# 1-MCU.net
KiCad netlist of a schematic drawn in Altium Designer
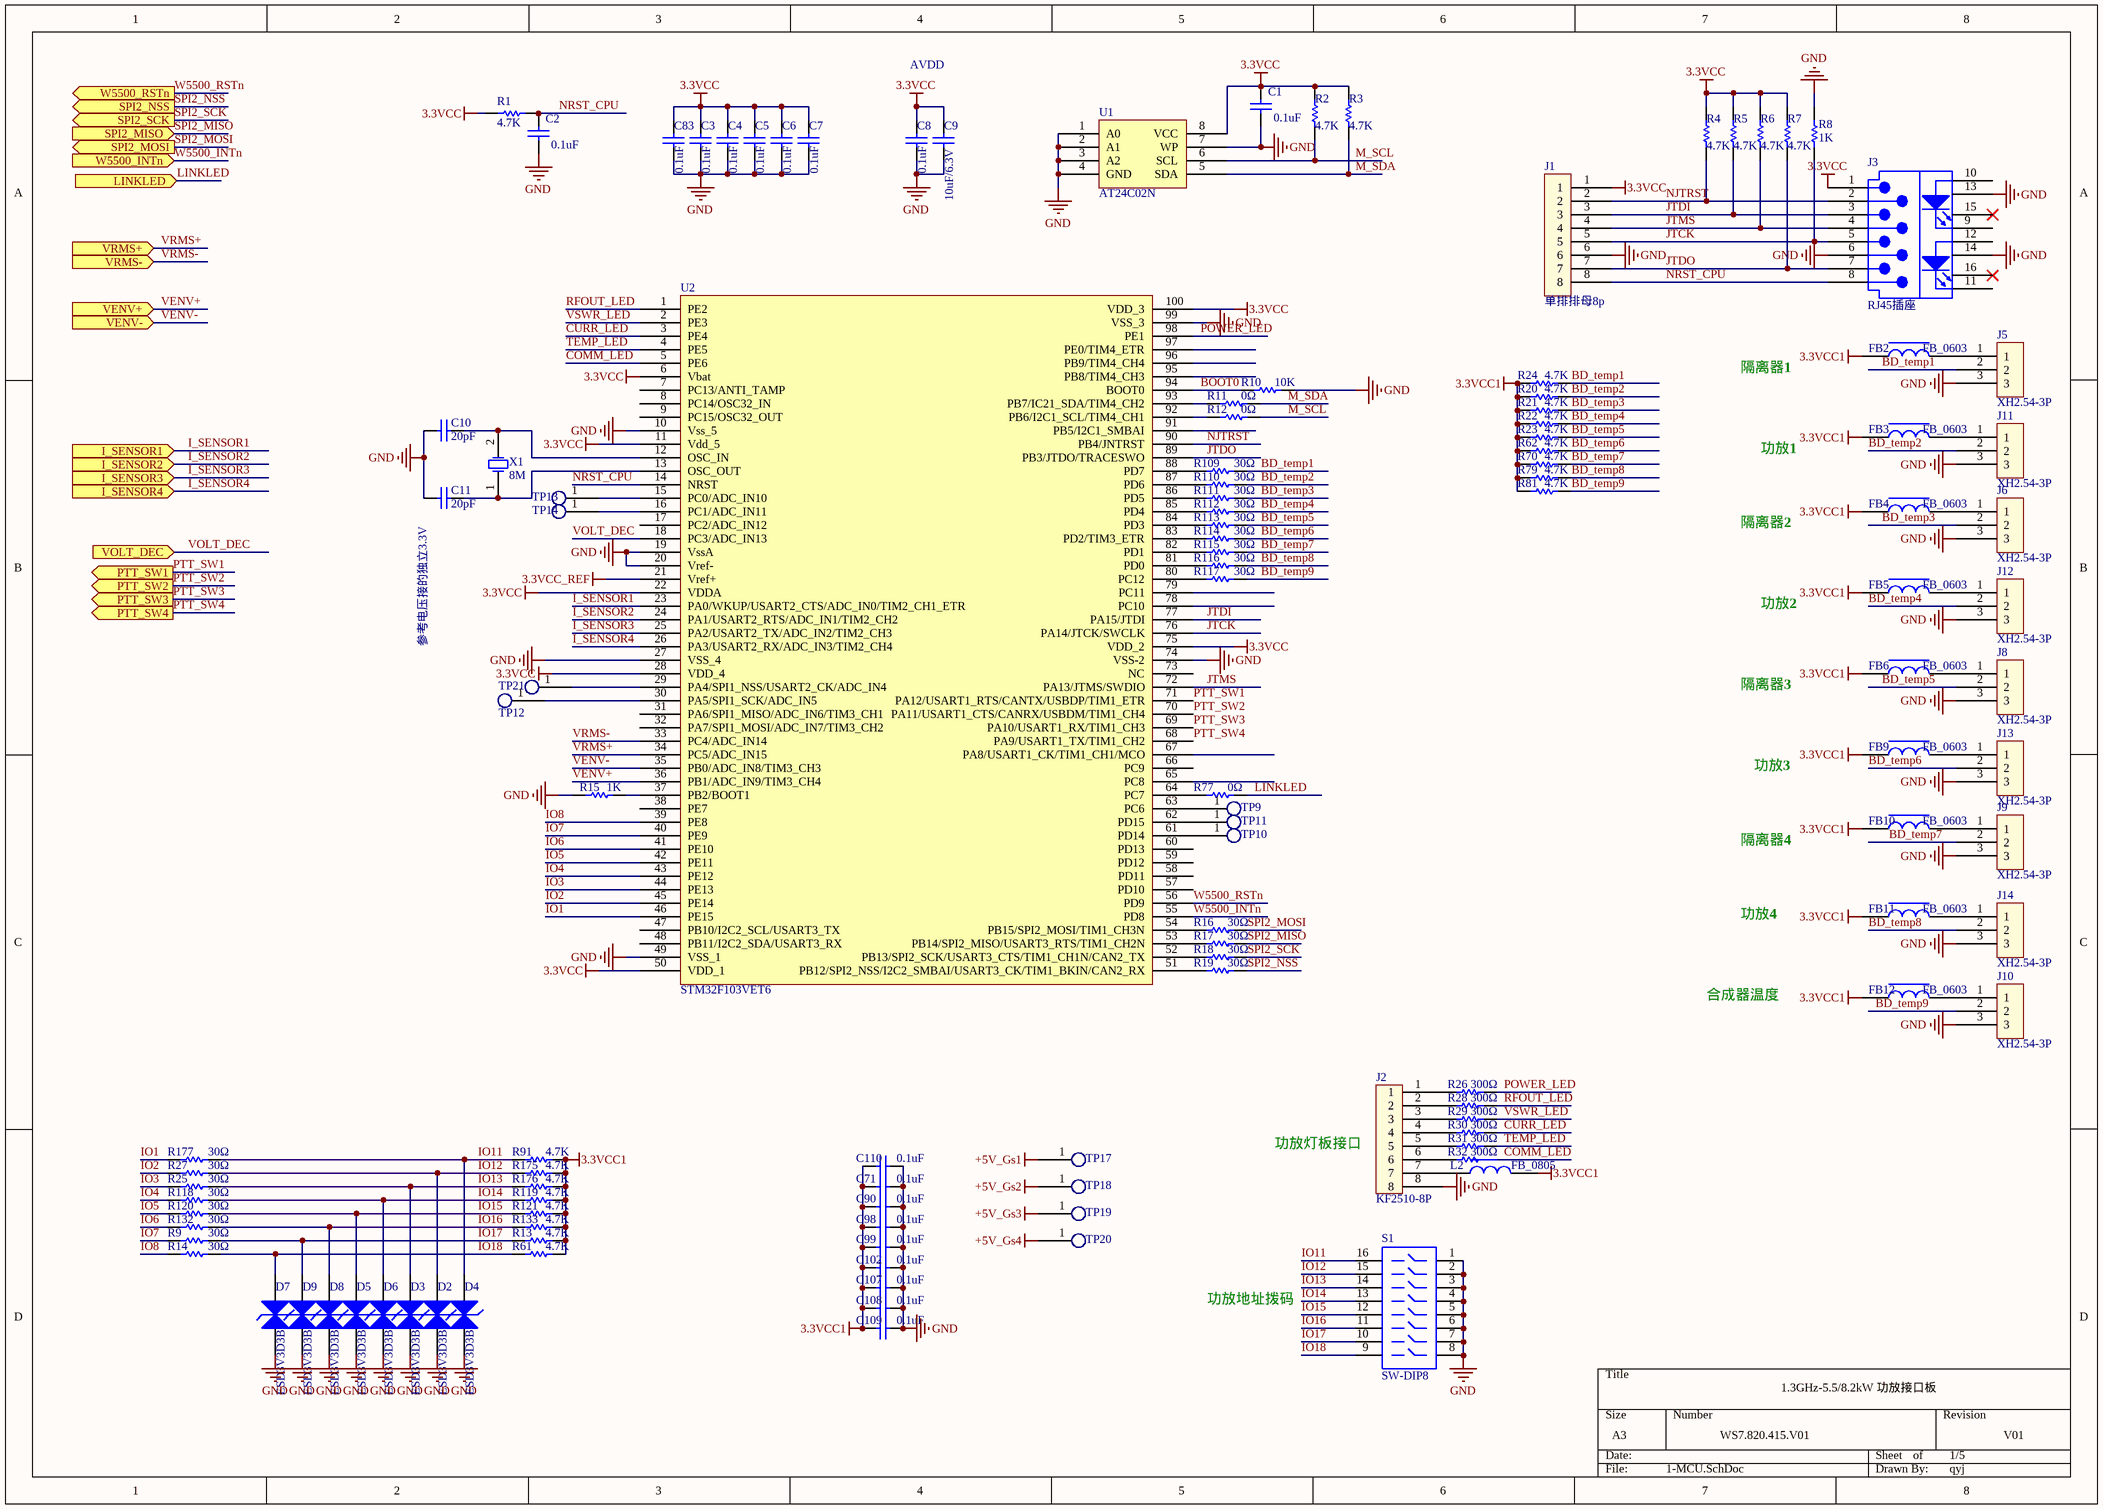
[diagram p0: 1-MCU.SchDoc]

(export (version "E")
  (design (tool "Eeschema 10.0.6"))
  (components
    (comp (ref "C1")
      (value "0.1uF")
      (footprint "C0603")
      (description "贴片电容_GRM188R71H104KA01D_0.1uF±10%,50V,0603")
      (libsource (lib "20贴片电容0603") (part "0.1uF贴片电容"))
    )
    (comp (ref "C2")
      (value "0.1uF")
      (footprint "C0603")
      (description "贴片电容_GRM188R71H104KA01D_0.1uF±10%,50V,0603")
      (libsource (lib "20贴片电容0603") (part "0.1uF贴片电容"))
    )
    (comp (ref "C3")
      (value "0.1uF")
      (footprint "C0603")
      (description "贴片电容_GRM188R71H104KA01D_0.1uF±10%,50V,0603")
      (libsource (lib "20贴片电容0603") (part "0.1uF贴片电容"))
    )
    (comp (ref "C4")
      (value "0.1uF")
      (footprint "C0603")
      (description "贴片电容_GRM188R71H104KA01D_0.1uF±10%,50V,0603")
      (libsource (lib "20贴片电容0603") (part "0.1uF贴片电容"))
    )
    (comp (ref "C5")
      (value "0.1uF")
      (footprint "C0603")
      (description "贴片电容_GRM188R71H104KA01D_0.1uF±10%,50V,0603")
      (libsource (lib "20贴片电容0603") (part "0.1uF贴片电容"))
    )
    (comp (ref "C6")
      (value "0.1uF")
      (footprint "C0603")
      (description "贴片电容_GRM188R71H104KA01D_0.1uF±10%,50V,0603")
      (libsource (lib "20贴片电容0603") (part "0.1uF贴片电容"))
    )
    (comp (ref "C7")
      (value "0.1uF")
      (footprint "C0603")
      (description "贴片电容_GRM188R71H104KA01D_0.1uF±10%,50V,0603")
      (libsource (lib "20贴片电容0603") (part "0.1uF贴片电容"))
    )
    (comp (ref "C8")
      (value "0.1uF")
      (footprint "C0603")
      (description "贴片电容_GRM188R71H104KA01D_0.1uF±10%,50V,0603")
      (libsource (lib "20贴片电容0603") (part "0.1uF贴片电容"))
    )
    (comp (ref "C9")
      (value "10uF/6.3V")
      (footprint "C0603")
      (description "贴片电容_GRM188R60J106ME47D_10uF±20%,6.3V,0603")
      (libsource (lib "20贴片电容0603") (part "10uF贴片电容"))
    )
    (comp (ref "C10")
      (value "20pF")
      (footprint "C0603")
      (description "贴片电容_GRM188C1H200JB01D_20pF±5%,50V,0603")
      (libsource (lib "20贴片电容0603") (part "20pF贴片电容"))
    )
    (comp (ref "C11")
      (value "20pF")
      (footprint "C0603")
      (description "贴片电容_GRM188C1H200JB01D_20pF±5%,50V,0603")
      (libsource (lib "20贴片电容0603") (part "20pF贴片电容"))
    )
    (comp (ref "C71")
      (value "0.1uF")
      (footprint "C0603")
      (description "GRM188R71H104KA01D")
      (fields (field (name "MPN") "MURATA"))
      (libsource (lib "20贴片电容0603") (part "0.1uF"))
    )
    (comp (ref "C83")
      (value "0.1uF")
      (footprint "C0603")
      (description "贴片电容_GRM188R71H104KA01D_0.1uF±10%,50V,0603")
      (libsource (lib "20贴片电容0603") (part "0.1uF贴片电容"))
    )
    (comp (ref "C90")
      (value "0.1uF")
      (footprint "C0603")
      (description "GRM188R71H104KA01D")
      (fields (field (name "MPN") "MURATA"))
      (libsource (lib "20贴片电容0603") (part "0.1uF"))
    )
    (comp (ref "C98")
      (value "0.1uF")
      (footprint "C0603")
      (description "GRM188R71H104KA01D")
      (fields (field (name "MPN") "MURATA"))
      (libsource (lib "20贴片电容0603") (part "0.1uF"))
    )
    (comp (ref "C99")
      (value "0.1uF")
      (footprint "C0603")
      (description "GRM188R71H104KA01D")
      (fields (field (name "MPN") "MURATA"))
      (libsource (lib "20贴片电容0603") (part "0.1uF"))
    )
    (comp (ref "C102")
      (value "0.1uF")
      (footprint "C0603")
      (description "GRM188R71H104KA01D")
      (fields (field (name "MPN") "MURATA"))
      (libsource (lib "20贴片电容0603") (part "0.1uF"))
    )
    (comp (ref "C107")
      (value "0.1uF")
      (footprint "C0603")
      (description "GRM188R71H104KA01D")
      (fields (field (name "MPN") "MURATA"))
      (libsource (lib "20贴片电容0603") (part "0.1uF"))
    )
    (comp (ref "C108")
      (value "0.1uF")
      (footprint "C0603")
      (description "GRM188R71H104KA01D")
      (fields (field (name "MPN") "MURATA"))
      (libsource (lib "20贴片电容0603") (part "0.1uF"))
    )
    (comp (ref "C109")
      (value "0.1uF")
      (footprint "C0603")
      (description "GRM188R71H104KA01D")
      (fields (field (name "MPN") "MURATA"))
      (libsource (lib "20贴片电容0603") (part "0.1uF"))
    )
    (comp (ref "C110")
      (value "0.1uF")
      (footprint "C0603")
      (description "GRM188R71H104KA01D")
      (fields (field (name "MPN") "MURATA"))
      (libsource (lib "20贴片电容0603") (part "0.1uF"))
    )
    (comp (ref "D2")
      (value "ESD3V3D3B")
      (footprint "SOD-323")
      (description "ESD_ESD3V3D3B_SOD-323,3.3V,双管")
      (libsource (lib "40二极管") (part "ESD5B5.0ST1G"))
    )
    (comp (ref "D3")
      (value "ESD3V3D3B")
      (footprint "SOD-323")
      (description "ESD_ESD3V3D3B_SOD-323,3.3V,双管")
      (libsource (lib "40二极管") (part "ESD5B5.0ST1G"))
    )
    (comp (ref "D4")
      (value "ESD3V3D3B")
      (footprint "SOD-323")
      (description "ESD_ESD3V3D3B_SOD-323,3.3V,双管")
      (libsource (lib "40二极管") (part "ESD5B5.0ST1G"))
    )
    (comp (ref "D5")
      (value "ESD3V3D3B")
      (footprint "SOD-323")
      (description "ESD_ESD3V3D3B_SOD-323,3.3V,双管")
      (libsource (lib "40二极管") (part "ESD5B5.0ST1G"))
    )
    (comp (ref "D6")
      (value "ESD3V3D3B")
      (footprint "SOD-323")
      (description "ESD_ESD3V3D3B_SOD-323,3.3V,双管")
      (libsource (lib "40二极管") (part "ESD5B5.0ST1G"))
    )
    (comp (ref "D7")
      (value "ESD3V3D3B")
      (footprint "SOD-323")
      (description "ESD_ESD3V3D3B_SOD-323,3.3V,双管")
      (libsource (lib "40二极管") (part "ESD5B5.0ST1G"))
    )
    (comp (ref "D8")
      (value "ESD3V3D3B")
      (footprint "SOD-323")
      (description "ESD_ESD3V3D3B_SOD-323,3.3V,双管")
      (libsource (lib "40二极管") (part "ESD5B5.0ST1G"))
    )
    (comp (ref "D9")
      (value "ESD3V3D3B")
      (footprint "SOD-323")
      (description "ESD_ESD3V3D3B_SOD-323,3.3V,双管")
      (libsource (lib "40二极管") (part "ESD5B5.0ST1G"))
    )
    (comp (ref "FB2")
      (value "FB_0603")
      (footprint "L0603")
      (description "贴片磁珠_100R,0603")
      (libsource (lib "32贴片磁珠0603") (part "0603贴片磁珠"))
    )
    (comp (ref "FB3")
      (value "FB_0603")
      (footprint "L0603")
      (description "贴片磁珠_100R,0603")
      (libsource (lib "32贴片磁珠0603") (part "0603贴片磁珠"))
    )
    (comp (ref "FB4")
      (value "FB_0603")
      (footprint "L0603")
      (description "贴片磁珠_100R,0603")
      (libsource (lib "32贴片磁珠0603") (part "0603贴片磁珠"))
    )
    (comp (ref "FB5")
      (value "FB_0603")
      (footprint "L0603")
      (description "贴片磁珠_100R,0603")
      (libsource (lib "32贴片磁珠0603") (part "0603贴片磁珠"))
    )
    (comp (ref "FB6")
      (value "FB_0603")
      (footprint "L0603")
      (description "贴片磁珠_100R,0603")
      (libsource (lib "32贴片磁珠0603") (part "0603贴片磁珠"))
    )
    (comp (ref "FB9")
      (value "FB_0603")
      (footprint "L0603")
      (description "贴片磁珠_100R,0603")
      (libsource (lib "32贴片磁珠0603") (part "0603贴片磁珠"))
    )
    (comp (ref "FB10")
      (value "FB_0603")
      (footprint "L0603")
      (description "贴片磁珠_100R,0603")
      (libsource (lib "32贴片磁珠0603") (part "0603贴片磁珠"))
    )
    (comp (ref "FB11")
      (value "FB_0603")
      (footprint "L0603")
      (description "贴片磁珠_100R,0603")
      (libsource (lib "32贴片磁珠0603") (part "0603贴片磁珠"))
    )
    (comp (ref "FB12")
      (value "FB_0603")
      (footprint "L0603")
      (description "贴片磁珠_100R,0603")
      (libsource (lib "32贴片磁珠0603") (part "0603贴片磁珠"))
    )
    (comp (ref "J1")
      (value "单排排母8p")
      (footprint "SIP8TM-2R54")
      (description "连接器_单排排母座8p_直插,间距2.54mm")
      (fields (field (name "MPN") "WS"))
      (libsource (lib "90-连接器") (part "8p-2.54单排母座"))
    )
    (comp (ref "J2")
      (value "KF2510-8P")
      (footprint "KF2510-8P -2R54-20R32x6R0-wanzhen")
      (description "连接器_KF2510-8P_90°弯针,间距2.54mm")
      (libsource (lib "91连接器") (part "KF2510-8P弯针"))
    )
    (comp (ref "J3")
      (value "RJ45插座")
      (footprint "RJ45TH-1x1-2R54-LED")
      (description "RJ45插座_1*1,带左黄右绿灯,弯脚")
      (fields (field (name "MPN") "朱迅"))
      (libsource (lib "91连接器") (part "RJ45弯脚带灯"))
    )
    (comp (ref "J5")
      (value "XH2.54-3P")
      (footprint "pcblib:XH2.54mm-10R0x7R0--zhizhen")
      (description "连接器_XH2.54-3P_弯针,间距2.54mm")
      (libsource (lib "91连接器") (part "XH2.54-3P"))
    )
    (comp (ref "J6")
      (value "XH2.54-3P")
      (footprint "pcblib:XH2.54mm-10R0x7R0--zhizhen")
      (description "连接器_XH2.54-3P_弯针,间距2.54mm")
      (libsource (lib "91连接器") (part "XH2.54-3P"))
    )
    (comp (ref "J8")
      (value "XH2.54-3P")
      (footprint "pcblib:XH2.54mm-10R0x7R0--zhizhen")
      (description "连接器_XH2.54-3P_弯针,间距2.54mm")
      (libsource (lib "91连接器") (part "XH2.54-3P"))
    )
    (comp (ref "J9")
      (value "XH2.54-3P")
      (footprint "pcblib:XH2.54mm-10R0x7R0--zhizhen")
      (description "连接器_XH2.54-3P_弯针,间距2.54mm")
      (libsource (lib "91连接器") (part "XH2.54-3P"))
    )
    (comp (ref "J10")
      (value "XH2.54-3P")
      (footprint "pcblib:XH2.54mm-10R0x7R0--zhizhen")
      (description "连接器_XH2.54-3P_弯针,间距2.54mm")
      (libsource (lib "91连接器") (part "XH2.54-3P"))
    )
    (comp (ref "J11")
      (value "XH2.54-3P")
      (footprint "XH2.54mm-10R0x7R0--zhizhen")
      (description "连接器_XH2.54-3P_弯针,间距2.54mm")
      (libsource (lib "91连接器") (part "XH2.54-3P"))
    )
    (comp (ref "J12")
      (value "XH2.54-3P")
      (footprint "XH2.54mm-10R0x7R0--zhizhen")
      (description "连接器_XH2.54-3P_弯针,间距2.54mm")
      (libsource (lib "91连接器") (part "XH2.54-3P"))
    )
    (comp (ref "J13")
      (value "XH2.54-3P")
      (footprint "XH2.54mm-10R0x7R0--zhizhen")
      (description "连接器_XH2.54-3P_弯针,间距2.54mm")
      (libsource (lib "91连接器") (part "XH2.54-3P"))
    )
    (comp (ref "J14")
      (value "XH2.54-3P")
      (footprint "XH2.54mm-10R0x7R0--zhizhen")
      (description "连接器_XH2.54-3P_弯针,间距2.54mm")
      (libsource (lib "91连接器") (part "XH2.54-3P"))
    )
    (comp (ref "L2")
      (value "FB_0805")
      (footprint "L0805")
      (description "贴片磁珠_600R,0805")
      (libsource (lib "33贴片磁珠0805") (part "0805贴片磁珠"))
    )
    (comp (ref "R1")
      (value "4.7K")
      (footprint "R0603")
      (description "贴片电阻_4.7K±5%,0603")
      (libsource (lib "10贴片电阻0603") (part "4.7K贴片电阻"))
    )
    (comp (ref "R2")
      (value "4.7K")
      (footprint "R0603")
      (description "贴片电阻_4.7K±5%,0603")
      (libsource (lib "10贴片电阻0603") (part "4.7K贴片电阻"))
    )
    (comp (ref "R3")
      (value "4.7K")
      (footprint "R0603")
      (description "贴片电阻_4.7K±5%,0603")
      (libsource (lib "10贴片电阻0603") (part "4.7K贴片电阻"))
    )
    (comp (ref "R4")
      (value "4.7K")
      (footprint "R0603")
      (description "贴片电阻_4.7K±5%,0603")
      (libsource (lib "10贴片电阻0603") (part "4.7K贴片电阻"))
    )
    (comp (ref "R5")
      (value "4.7K")
      (footprint "R0603")
      (description "贴片电阻_4.7K±5%,0603")
      (libsource (lib "10贴片电阻0603") (part "4.7K贴片电阻"))
    )
    (comp (ref "R6")
      (value "4.7K")
      (footprint "R0603")
      (description "贴片电阻_4.7K±5%,0603")
      (libsource (lib "10贴片电阻0603") (part "4.7K贴片电阻"))
    )
    (comp (ref "R7")
      (value "4.7K")
      (footprint "R0603")
      (description "贴片电阻_4.7K±5%,0603")
      (libsource (lib "10贴片电阻0603") (part "4.7K贴片电阻"))
    )
    (comp (ref "R8")
      (value "1K")
      (footprint "R0603")
      (description "贴片电阻_1K±5%,0603")
      (libsource (lib "10贴片电阻0603") (part "1K贴片电阻"))
    )
    (comp (ref "R9")
      (value "30Ω")
      (footprint "R0603")
      (description "贴片电阻_30Ω±5%,0603")
      (libsource (lib "10贴片电阻0603") (part "0Ω贴片电阻"))
    )
    (comp (ref "R10")
      (value "10K")
      (footprint "R0603")
      (description "贴片电阻_10K±5%,0603")
      (libsource (lib "10贴片电阻0603") (part "10K贴片电阻"))
    )
    (comp (ref "R11")
      (value "0Ω")
      (footprint "R0603")
      (description "贴片电阻_0Ω±5%,0603")
      (libsource (lib "10贴片电阻0603") (part "0Ω贴片电阻"))
    )
    (comp (ref "R12")
      (value "0Ω")
      (footprint "R0603")
      (description "贴片电阻_0Ω±5%,0603")
      (libsource (lib "10贴片电阻0603") (part "0Ω贴片电阻"))
    )
    (comp (ref "R13")
      (value "4.7K")
      (footprint "R0603")
      (description "贴片电阻_4.7K±5%,0603")
      (libsource (lib "10贴片电阻0603") (part "4.7K贴片电阻"))
    )
    (comp (ref "R14")
      (value "30Ω")
      (footprint "R0603")
      (description "贴片电阻_30Ω±5%,0603")
      (libsource (lib "10贴片电阻0603") (part "0Ω贴片电阻"))
    )
    (comp (ref "R15")
      (value "1K")
      (footprint "R0603")
      (description "贴片电阻_1K±5%,0603")
      (libsource (lib "10贴片电阻0603") (part "1K贴片电阻"))
    )
    (comp (ref "R16")
      (value "30Ω")
      (footprint "R0603")
      (description "贴片电阻_30Ω±5%,0603")
      (libsource (lib "10贴片电阻0603") (part "30Ω贴片电阻"))
    )
    (comp (ref "R17")
      (value "30Ω")
      (footprint "R0603")
      (description "贴片电阻_30Ω±5%,0603")
      (libsource (lib "10贴片电阻0603") (part "30Ω贴片电阻"))
    )
    (comp (ref "R18")
      (value "30Ω")
      (footprint "R0603")
      (description "贴片电阻_30Ω±5%,0603")
      (libsource (lib "10贴片电阻0603") (part "30Ω贴片电阻"))
    )
    (comp (ref "R19")
      (value "30Ω")
      (footprint "R0603")
      (description "贴片电阻_30Ω±5%,0603")
      (libsource (lib "10贴片电阻0603") (part "30Ω贴片电阻"))
    )
    (comp (ref "R20")
      (value "4.7K")
      (footprint "R0603")
      (description "贴片电阻_4.7K±5%,0603")
      (libsource (lib "10贴片电阻0603") (part "4.7K贴片电阻"))
    )
    (comp (ref "R21")
      (value "4.7K")
      (footprint "R0603")
      (description "贴片电阻_4.7K±5%,0603")
      (libsource (lib "10贴片电阻0603") (part "4.7K贴片电阻"))
    )
    (comp (ref "R22")
      (value "4.7K")
      (footprint "R0603")
      (description "贴片电阻_4.7K±5%,0603")
      (libsource (lib "10贴片电阻0603") (part "4.7K贴片电阻"))
    )
    (comp (ref "R23")
      (value "4.7K")
      (footprint "R0603")
      (description "贴片电阻_4.7K±5%,0603")
      (libsource (lib "10贴片电阻0603") (part "4.7K贴片电阻"))
    )
    (comp (ref "R24")
      (value "4.7K")
      (footprint "R0603")
      (description "贴片电阻_4.7K±5%,0603")
      (libsource (lib "10贴片电阻0603") (part "4.7K贴片电阻"))
    )
    (comp (ref "R25")
      (value "30Ω")
      (footprint "R0603")
      (description "贴片电阻_30Ω±5%,0603")
      (libsource (lib "10贴片电阻0603") (part "0Ω贴片电阻"))
    )
    (comp (ref "R26")
      (value "300Ω")
      (footprint "R0603")
      (description "贴片电阻_300Ω±5%,0603")
      (libsource (lib "10贴片电阻0603") (part "300Ω贴片电阻"))
    )
    (comp (ref "R27")
      (value "30Ω")
      (footprint "R0603")
      (description "贴片电阻_30Ω±5%,0603")
      (libsource (lib "10贴片电阻0603") (part "0Ω贴片电阻"))
    )
    (comp (ref "R28")
      (value "300Ω")
      (footprint "R0603")
      (description "贴片电阻_300Ω±5%,0603")
      (libsource (lib "10贴片电阻0603") (part "300Ω贴片电阻"))
    )
    (comp (ref "R29")
      (value "300Ω")
      (footprint "R0603")
      (description "贴片电阻_300Ω±5%,0603")
      (libsource (lib "10贴片电阻0603") (part "300Ω贴片电阻"))
    )
    (comp (ref "R30")
      (value "300Ω")
      (footprint "R0603")
      (description "贴片电阻_300Ω±5%,0603")
      (libsource (lib "10贴片电阻0603") (part "300Ω贴片电阻"))
    )
    (comp (ref "R31")
      (value "300Ω")
      (footprint "R0603")
      (description "贴片电阻_300Ω±5%,0603")
      (libsource (lib "10贴片电阻0603") (part "300Ω贴片电阻"))
    )
    (comp (ref "R32")
      (value "300Ω")
      (footprint "R0603")
      (description "贴片电阻_300Ω±5%,0603")
      (libsource (lib "10贴片电阻0603") (part "300Ω贴片电阻"))
    )
    (comp (ref "R61")
      (value "4.7K")
      (footprint "R0603")
      (description "贴片电阻_4.7K±5%,0603")
      (libsource (lib "10贴片电阻0603") (part "4.7K贴片电阻"))
    )
    (comp (ref "R62")
      (value "4.7K")
      (footprint "R0603")
      (description "贴片电阻_4.7K±5%,0603")
      (libsource (lib "10贴片电阻0603") (part "4.7K贴片电阻"))
    )
    (comp (ref "R70")
      (value "4.7K")
      (footprint "R0603")
      (description "贴片电阻_4.7K±5%,0603")
      (libsource (lib "10贴片电阻0603") (part "4.7K贴片电阻"))
    )
    (comp (ref "R77")
      (value "0Ω")
      (footprint "R0603")
      (description "贴片电阻_0Ω±5%,0603")
      (libsource (lib "10贴片电阻0603") (part "0Ω贴片电阻"))
    )
    (comp (ref "R79")
      (value "4.7K")
      (footprint "R0603")
      (description "贴片电阻_4.7K±5%,0603")
      (libsource (lib "10贴片电阻0603") (part "4.7K贴片电阻"))
    )
    (comp (ref "R81")
      (value "4.7K")
      (footprint "R0603")
      (description "贴片电阻_4.7K±5%,0603")
      (libsource (lib "10贴片电阻0603") (part "4.7K贴片电阻"))
    )
    (comp (ref "R91")
      (value "4.7K")
      (footprint "R0603")
      (description "贴片电阻_4.7K±5%,0603")
      (libsource (lib "10贴片电阻0603") (part "4.7K贴片电阻"))
    )
    (comp (ref "R109")
      (value "30Ω")
      (footprint "R0603")
      (description "贴片电阻_30Ω±5%,0603")
      (libsource (lib "10贴片电阻0603") (part "30Ω贴片电阻"))
    )
    (comp (ref "R110")
      (value "30Ω")
      (footprint "R0603")
      (description "贴片电阻_30Ω±5%,0603")
      (libsource (lib "10贴片电阻0603") (part "30Ω贴片电阻"))
    )
    (comp (ref "R111")
      (value "30Ω")
      (footprint "R0603")
      (description "贴片电阻_30Ω±5%,0603")
      (libsource (lib "10贴片电阻0603") (part "30Ω贴片电阻"))
    )
    (comp (ref "R112")
      (value "30Ω")
      (footprint "R0603")
      (description "贴片电阻_30Ω±5%,0603")
      (libsource (lib "10贴片电阻0603") (part "30Ω贴片电阻"))
    )
    (comp (ref "R113")
      (value "30Ω")
      (footprint "R0603")
      (description "贴片电阻_30Ω±5%,0603")
      (libsource (lib "10贴片电阻0603") (part "30Ω贴片电阻"))
    )
    (comp (ref "R114")
      (value "30Ω")
      (footprint "R0603")
      (description "贴片电阻_30Ω±5%,0603")
      (libsource (lib "10贴片电阻0603") (part "30Ω贴片电阻"))
    )
    (comp (ref "R115")
      (value "30Ω")
      (footprint "R0603")
      (description "贴片电阻_30Ω±5%,0603")
      (libsource (lib "10贴片电阻0603") (part "30Ω贴片电阻"))
    )
    (comp (ref "R116")
      (value "30Ω")
      (footprint "R0603")
      (description "贴片电阻_30Ω±5%,0603")
      (libsource (lib "10贴片电阻0603") (part "30Ω贴片电阻"))
    )
    (comp (ref "R117")
      (value "30Ω")
      (footprint "R0603")
      (description "贴片电阻_30Ω±5%,0603")
      (libsource (lib "10贴片电阻0603") (part "30Ω贴片电阻"))
    )
    (comp (ref "R118")
      (value "30Ω")
      (footprint "R0603")
      (description "贴片电阻_30Ω±5%,0603")
      (libsource (lib "10贴片电阻0603") (part "0Ω贴片电阻"))
    )
    (comp (ref "R119")
      (value "4.7K")
      (footprint "R0603")
      (description "贴片电阻_4.7K±5%,0603")
      (libsource (lib "10贴片电阻0603") (part "4.7K贴片电阻"))
    )
    (comp (ref "R120")
      (value "30Ω")
      (footprint "R0603")
      (description "贴片电阻_30Ω±5%,0603")
      (libsource (lib "10贴片电阻0603") (part "0Ω贴片电阻"))
    )
    (comp (ref "R121")
      (value "4.7K")
      (footprint "R0603")
      (description "贴片电阻_4.7K±5%,0603")
      (libsource (lib "10贴片电阻0603") (part "4.7K贴片电阻"))
    )
    (comp (ref "R132")
      (value "30Ω")
      (footprint "R0603")
      (description "贴片电阻_30Ω±5%,0603")
      (libsource (lib "10贴片电阻0603") (part "0Ω贴片电阻"))
    )
    (comp (ref "R133")
      (value "4.7K")
      (footprint "R0603")
      (description "贴片电阻_4.7K±5%,0603")
      (libsource (lib "10贴片电阻0603") (part "4.7K贴片电阻"))
    )
    (comp (ref "R175")
      (value "4.7K")
      (footprint "R0603")
      (description "贴片电阻_4.7K±5%,0603")
      (libsource (lib "10贴片电阻0603") (part "4.7K贴片电阻"))
    )
    (comp (ref "R176")
      (value "4.7K")
      (footprint "R0603")
      (description "贴片电阻_4.7K±5%,0603")
      (libsource (lib "10贴片电阻0603") (part "4.7K贴片电阻"))
    )
    (comp (ref "R177")
      (value "30Ω")
      (footprint "R0603")
      (description "贴片电阻_30Ω±5%,0603")
      (libsource (lib "10贴片电阻0603") (part "0Ω贴片电阻"))
    )
    (comp (ref "S1")
      (value "SW-DIP8")
      (footprint "DIP-16-KEY")
      (description "4009 Series DIP Switch, Raised actuator")
      (fields (field (name "PUBLISHER") "Altium Limited"))
      (libsource (lib "Miscellaneous Devices") (part "SW-DIP8"))
    )
    (comp (ref "TP9")
      (value "TEST")
      (footprint "TP0R8")
      (description "表贴测试点0.8mm")
      (libsource (lib "92-其他（穿心电容，test等）") (part "TP0.8mm"))
    )
    (comp (ref "TP10")
      (value "TEST")
      (footprint "TP0R8")
      (description "表贴测试点0.8mm")
      (libsource (lib "92-其他（穿心电容，test等）") (part "TP0.8mm"))
    )
    (comp (ref "TP11")
      (value "TEST")
      (footprint "TP0R8")
      (description "表贴测试点0.8mm")
      (libsource (lib "92-其他（穿心电容，test等）") (part "TP0.8mm"))
    )
    (comp (ref "TP12")
      (value "TEST")
      (footprint "TP0R8")
      (description "表贴测试点0.8mm")
      (libsource (lib "92-其他（穿心电容，test等）") (part "TP0.8mm"))
    )
    (comp (ref "TP13")
      (value "TEST")
      (footprint "TP0R8")
      (description "表贴测试点0.8mm")
      (libsource (lib "92-其他（穿心电容，test等）") (part "TP0.8mm"))
    )
    (comp (ref "TP14")
      (value "TEST")
      (footprint "TP0R8")
      (description "表贴测试点0.8mm")
      (libsource (lib "92-其他（穿心电容，test等）") (part "TP0.8mm"))
    )
    (comp (ref "TP17")
      (value "~")
      (footprint "TP2R54mm")
      (description "表贴测试点1mm")
      (libsource (lib "92-其他（穿心电容，test等）") (part "TP2mm"))
    )
    (comp (ref "TP18")
      (value "~")
      (footprint "TP2R54mm")
      (description "表贴测试点1mm")
      (libsource (lib "92-其他（穿心电容，test等）") (part "TP2mm"))
    )
    (comp (ref "TP19")
      (value "~")
      (footprint "TP2R54mm")
      (description "表贴测试点1mm")
      (libsource (lib "92-其他（穿心电容，test等）") (part "TP2mm"))
    )
    (comp (ref "TP20")
      (value "~")
      (footprint "TP2R54mm")
      (description "表贴测试点1mm")
      (libsource (lib "92-其他（穿心电容，test等）") (part "TP2mm"))
    )
    (comp (ref "TP21")
      (value "TEST")
      (footprint "TP0R8")
      (description "表贴测试点0.8mm")
      (libsource (lib "92-其他（穿心电容，test等）") (part "TP0.8mm"))
    )
    (comp (ref "U1")
      (value "AT24C02N")
      (footprint "SOIC8_1R27_3R9x4R9")
      (description "EEPROM_AT24C02N_SOIC8")
      (libsource (lib "82存储器") (part "AT24C02N"))
    )
    (comp (ref "U2")
      (value "STM32F103VET6")
      (footprint "LQFP100_0R5_14x14")
      (description "MCU_STM32F103VET6_32 bit, LQFP100")
      (libsource (lib "71单片机") (part "STM32F103VET"))
    )
    (comp (ref "X1")
      (value "8M")
      (footprint "CRY2SM-6R0x3R5")
      (description "贴片无源晶体_8MHz,封装6035")
      (libsource (lib "60振荡器") (part "8M贴片无源晶体"))
    )
  )
  (nets
    (net (code "1") (name "+5V_Gs1") (class "Default")
      (node (ref "TP17") (pin "1") (pinfunction "TP_1") (pintype "passive"))
    )
    (net (code "2") (name "+5V_Gs2") (class "Default")
      (node (ref "TP18") (pin "1") (pinfunction "TP_1") (pintype "passive"))
    )
    (net (code "3") (name "+5V_Gs3") (class "Default")
      (node (ref "TP19") (pin "1") (pinfunction "TP_1") (pintype "passive"))
    )
    (net (code "4") (name "+5V_Gs4") (class "Default")
      (node (ref "TP20") (pin "1") (pinfunction "TP_1") (pintype "passive"))
    )
    (net (code "5") (name "/BD_temp1") (class "Default")
      (node (ref "J5") (pin "2") (pinfunction "2_2") (pintype "passive"))
      (node (ref "R109") (pin "2") (pinfunction "2_2") (pintype "passive"))
      (node (ref "R24") (pin "2") (pinfunction "2_2") (pintype "passive"))
    )
    (net (code "6") (name "/BD_temp2") (class "Default")
      (node (ref "J11") (pin "2") (pinfunction "2_2") (pintype "passive"))
      (node (ref "R110") (pin "2") (pinfunction "2_2") (pintype "passive"))
      (node (ref "R20") (pin "2") (pinfunction "2_2") (pintype "passive"))
    )
    (net (code "7") (name "/BD_temp3") (class "Default")
      (node (ref "J6") (pin "2") (pinfunction "2_2") (pintype "passive"))
      (node (ref "R111") (pin "2") (pinfunction "2_2") (pintype "passive"))
      (node (ref "R21") (pin "2") (pinfunction "2_2") (pintype "passive"))
    )
    (net (code "8") (name "/BD_temp4") (class "Default")
      (node (ref "J12") (pin "2") (pinfunction "2_2") (pintype "passive"))
      (node (ref "R112") (pin "2") (pinfunction "2_2") (pintype "passive"))
      (node (ref "R22") (pin "2") (pinfunction "2_2") (pintype "passive"))
    )
    (net (code "9") (name "/BD_temp5") (class "Default")
      (node (ref "J8") (pin "2") (pinfunction "2_2") (pintype "passive"))
      (node (ref "R113") (pin "2") (pinfunction "2_2") (pintype "passive"))
      (node (ref "R23") (pin "2") (pinfunction "2_2") (pintype "passive"))
    )
    (net (code "10") (name "/BD_temp6") (class "Default")
      (node (ref "J13") (pin "2") (pinfunction "2_2") (pintype "passive"))
      (node (ref "R114") (pin "2") (pinfunction "2_2") (pintype "passive"))
      (node (ref "R62") (pin "2") (pinfunction "2_2") (pintype "passive"))
    )
    (net (code "11") (name "/BD_temp7") (class "Default")
      (node (ref "J9") (pin "2") (pinfunction "2_2") (pintype "passive"))
      (node (ref "R115") (pin "2") (pinfunction "2_2") (pintype "passive"))
      (node (ref "R70") (pin "2") (pinfunction "2_2") (pintype "passive"))
    )
    (net (code "12") (name "/BD_temp8") (class "Default")
      (node (ref "J14") (pin "2") (pinfunction "2_2") (pintype "passive"))
      (node (ref "R116") (pin "2") (pinfunction "2_2") (pintype "passive"))
      (node (ref "R79") (pin "2") (pinfunction "2_2") (pintype "passive"))
    )
    (net (code "13") (name "/BD_temp9") (class "Default")
      (node (ref "J10") (pin "2") (pinfunction "2_2") (pintype "passive"))
      (node (ref "R117") (pin "2") (pinfunction "2_2") (pintype "passive"))
      (node (ref "R81") (pin "2") (pinfunction "2_2") (pintype "passive"))
    )
    (net (code "14") (name "/BOOT0") (class "Default")
      (node (ref "R10") (pin "2") (pinfunction "2_2") (pintype "passive"))
      (node (ref "U2") (pin "94") (pinfunction "BOOT0_94") (pintype "passive"))
    )
    (net (code "15") (name "/COMM_LED") (class "Default")
      (node (ref "R32") (pin "2") (pinfunction "2_2") (pintype "passive"))
      (node (ref "U2") (pin "5") (pinfunction "PE6_5") (pintype "passive"))
    )
    (net (code "16") (name "/CURR_LED") (class "Default")
      (node (ref "R30") (pin "2") (pinfunction "2_2") (pintype "passive"))
      (node (ref "U2") (pin "3") (pinfunction "PE4_3") (pintype "passive"))
    )
    (net (code "17") (name "/IO1") (class "Default")
      (node (ref "R177") (pin "2") (pinfunction "2_2") (pintype "passive"))
      (node (ref "U2") (pin "46") (pinfunction "PE15_46") (pintype "passive"))
    )
    (net (code "18") (name "/IO2") (class "Default")
      (node (ref "R27") (pin "2") (pinfunction "2_2") (pintype "passive"))
      (node (ref "U2") (pin "45") (pinfunction "PE14_45") (pintype "passive"))
    )
    (net (code "19") (name "/IO3") (class "Default")
      (node (ref "R25") (pin "2") (pinfunction "2_2") (pintype "passive"))
      (node (ref "U2") (pin "44") (pinfunction "PE13_44") (pintype "passive"))
    )
    (net (code "20") (name "/IO4") (class "Default")
      (node (ref "R118") (pin "2") (pinfunction "2_2") (pintype "passive"))
      (node (ref "U2") (pin "43") (pinfunction "PE12_43") (pintype "passive"))
    )
    (net (code "21") (name "/IO5") (class "Default")
      (node (ref "R120") (pin "2") (pinfunction "2_2") (pintype "passive"))
      (node (ref "U2") (pin "42") (pinfunction "PE11_42") (pintype "passive"))
    )
    (net (code "22") (name "/IO6") (class "Default")
      (node (ref "R132") (pin "2") (pinfunction "2_2") (pintype "passive"))
      (node (ref "U2") (pin "41") (pinfunction "PE10_41") (pintype "passive"))
    )
    (net (code "23") (name "/IO7") (class "Default")
      (node (ref "R9") (pin "2") (pinfunction "2_2") (pintype "passive"))
      (node (ref "U2") (pin "40") (pinfunction "PE9_40") (pintype "passive"))
    )
    (net (code "24") (name "/IO8") (class "Default")
      (node (ref "R14") (pin "2") (pinfunction "2_2") (pintype "passive"))
      (node (ref "U2") (pin "39") (pinfunction "PE8_39") (pintype "passive"))
    )
    (net (code "25") (name "/IO11") (class "Default")
      (node (ref "D4") (pin "1") (pinfunction "1_1") (pintype "passive"))
      (node (ref "R177") (pin "1") (pinfunction "1_1") (pintype "passive"))
      (node (ref "R91") (pin "2") (pinfunction "2_2") (pintype "passive"))
      (node (ref "S1") (pin "16") (pinfunction "16_16") (pintype "passive"))
    )
    (net (code "26") (name "/IO12") (class "Default")
      (node (ref "D2") (pin "1") (pinfunction "1_1") (pintype "passive"))
      (node (ref "R175") (pin "2") (pinfunction "2_2") (pintype "passive"))
      (node (ref "R27") (pin "1") (pinfunction "1_1") (pintype "passive"))
      (node (ref "S1") (pin "15") (pinfunction "15_15") (pintype "passive"))
    )
    (net (code "27") (name "/IO13") (class "Default")
      (node (ref "D3") (pin "1") (pinfunction "1_1") (pintype "passive"))
      (node (ref "R176") (pin "2") (pinfunction "2_2") (pintype "passive"))
      (node (ref "R25") (pin "1") (pinfunction "1_1") (pintype "passive"))
      (node (ref "S1") (pin "14") (pinfunction "14_14") (pintype "passive"))
    )
    (net (code "28") (name "/IO14") (class "Default")
      (node (ref "D6") (pin "1") (pinfunction "1_1") (pintype "passive"))
      (node (ref "R118") (pin "1") (pinfunction "1_1") (pintype "passive"))
      (node (ref "R119") (pin "2") (pinfunction "2_2") (pintype "passive"))
      (node (ref "S1") (pin "13") (pinfunction "13_13") (pintype "passive"))
    )
    (net (code "29") (name "/IO15") (class "Default")
      (node (ref "D5") (pin "1") (pinfunction "1_1") (pintype "passive"))
      (node (ref "R120") (pin "1") (pinfunction "1_1") (pintype "passive"))
      (node (ref "R121") (pin "2") (pinfunction "2_2") (pintype "passive"))
      (node (ref "S1") (pin "12") (pinfunction "12_12") (pintype "passive"))
    )
    (net (code "30") (name "/IO16") (class "Default")
      (node (ref "D8") (pin "1") (pinfunction "1_1") (pintype "passive"))
      (node (ref "R132") (pin "1") (pinfunction "1_1") (pintype "passive"))
      (node (ref "R133") (pin "2") (pinfunction "2_2") (pintype "passive"))
      (node (ref "S1") (pin "11") (pinfunction "11_11") (pintype "passive"))
    )
    (net (code "31") (name "/IO17") (class "Default")
      (node (ref "D9") (pin "1") (pinfunction "1_1") (pintype "passive"))
      (node (ref "R13") (pin "2") (pinfunction "2_2") (pintype "passive"))
      (node (ref "R9") (pin "1") (pinfunction "1_1") (pintype "passive"))
      (node (ref "S1") (pin "10") (pinfunction "10_10") (pintype "passive"))
    )
    (net (code "32") (name "/IO18") (class "Default")
      (node (ref "D7") (pin "1") (pinfunction "1_1") (pintype "passive"))
      (node (ref "R14") (pin "1") (pinfunction "1_1") (pintype "passive"))
      (node (ref "R61") (pin "2") (pinfunction "2_2") (pintype "passive"))
      (node (ref "S1") (pin "9") (pinfunction "9_9") (pintype "passive"))
    )
    (net (code "33") (name "/I_SENSOR1") (class "Default")
      (node (ref "U2") (pin "23") (pinfunction "PA0/WKUP/USART2_CTS/ADC_IN0/TIM2_CH1_ETR_23") (pintype "passive"))
    )
    (net (code "34") (name "/I_SENSOR2") (class "Default")
      (node (ref "U2") (pin "24") (pinfunction "PA1/USART2_RTS/ADC_IN1/TIM2_CH2_24") (pintype "passive"))
    )
    (net (code "35") (name "/I_SENSOR3") (class "Default")
      (node (ref "U2") (pin "25") (pinfunction "PA2/USART2_TX/ADC_IN2/TIM2_CH3_25") (pintype "passive"))
    )
    (net (code "36") (name "/I_SENSOR4") (class "Default")
      (node (ref "U2") (pin "26") (pinfunction "PA3/USART2_RX/ADC_IN3/TIM2_CH4_26") (pintype "passive"))
    )
    (net (code "37") (name "/JTCK") (class "Default")
      (node (ref "J1") (pin "5") (pinfunction "5_5") (pintype "passive"))
      (node (ref "J3") (pin "5") (pinfunction "NC_5") (pintype "passive"))
      (node (ref "R8") (pin "2") (pinfunction "2_2") (pintype "passive"))
      (node (ref "U2") (pin "76") (pinfunction "PA14/JTCK/SWCLK_76") (pintype "passive"))
    )
    (net (code "38") (name "/JTDI") (class "Default")
      (node (ref "J1") (pin "3") (pinfunction "3_3") (pintype "passive"))
      (node (ref "J3") (pin "3") (pinfunction "RX+_3") (pintype "passive"))
      (node (ref "R5") (pin "1") (pinfunction "1_1") (pintype "passive"))
      (node (ref "U2") (pin "77") (pinfunction "PA15/JTDI_77") (pintype "passive"))
    )
    (net (code "39") (name "/JTDO") (class "Default")
      (node (ref "J1") (pin "7") (pinfunction "7_7") (pintype "passive"))
      (node (ref "J3") (pin "7") (pinfunction "NC_7") (pintype "passive"))
      (node (ref "R7") (pin "1") (pinfunction "1_1") (pintype "passive"))
      (node (ref "U2") (pin "89") (pinfunction "PB3/JTDO/TRACESWO_89") (pintype "passive"))
    )
    (net (code "40") (name "/JTMS") (class "Default")
      (node (ref "J1") (pin "4") (pinfunction "4_4") (pintype "passive"))
      (node (ref "J3") (pin "4") (pinfunction "NC_4") (pintype "passive"))
      (node (ref "R6") (pin "1") (pinfunction "1_1") (pintype "passive"))
      (node (ref "U2") (pin "72") (pinfunction "PA13/JTMS/SWDIO_72") (pintype "passive"))
    )
    (net (code "41") (name "/LINKLED") (class "Default")
      (node (ref "R77") (pin "2") (pinfunction "2_2") (pintype "passive"))
    )
    (net (code "42") (name "/M_SCL") (class "Default")
      (node (ref "R12") (pin "2") (pinfunction "2_2") (pintype "passive"))
      (node (ref "R2") (pin "1") (pinfunction "1_1") (pintype "passive"))
      (node (ref "U1") (pin "6") (pinfunction "SCL_6") (pintype "passive"))
    )
    (net (code "43") (name "/M_SDA") (class "Default")
      (node (ref "R11") (pin "2") (pinfunction "2_2") (pintype "passive"))
      (node (ref "R3") (pin "1") (pinfunction "1_1") (pintype "passive"))
      (node (ref "U1") (pin "5") (pinfunction "SDA_5") (pintype "passive"))
    )
    (net (code "44") (name "/NJTRST") (class "Default")
      (node (ref "J1") (pin "2") (pinfunction "2_2") (pintype "passive"))
      (node (ref "J3") (pin "2") (pinfunction "TX-_2") (pintype "passive"))
      (node (ref "R4") (pin "1") (pinfunction "1_1") (pintype "passive"))
      (node (ref "U2") (pin "90") (pinfunction "PB4/JNTRST_90") (pintype "passive"))
    )
    (net (code "45") (name "/NRST_CPU") (class "Default")
      (node (ref "C2") (pin "2") (pinfunction "2_2") (pintype "passive"))
      (node (ref "J1") (pin "8") (pinfunction "8_8") (pintype "passive"))
      (node (ref "J3") (pin "8") (pinfunction "NC_8") (pintype "passive"))
      (node (ref "R1") (pin "1") (pinfunction "1_1") (pintype "passive"))
      (node (ref "U2") (pin "14") (pinfunction "NRST_14") (pintype "passive"))
    )
    (net (code "46") (name "/POWER_LED") (class "Default")
      (node (ref "R26") (pin "2") (pinfunction "2_2") (pintype "passive"))
      (node (ref "U2") (pin "98") (pinfunction "PE1_98") (pintype "passive"))
    )
    (net (code "47") (name "/PTT_SW1") (class "Default")
      (node (ref "U2") (pin "71") (pinfunction "PA12/USART1_RTS/CANTX/USBDP/TIM1_ETR_71") (pintype "passive"))
    )
    (net (code "48") (name "/PTT_SW2") (class "Default")
      (node (ref "U2") (pin "70") (pinfunction "PA11/USART1_CTS/CANRX/USBDM/TIM1_CH4_70") (pintype "passive"))
    )
    (net (code "49") (name "/PTT_SW3") (class "Default")
      (node (ref "U2") (pin "69") (pinfunction "PA10/USART1_RX/TIM1_CH3_69") (pintype "passive"))
    )
    (net (code "50") (name "/PTT_SW4") (class "Default")
      (node (ref "U2") (pin "68") (pinfunction "PA9/USART1_TX/TIM1_CH2_68") (pintype "passive"))
    )
    (net (code "51") (name "/RFOUT_LED") (class "Default")
      (node (ref "R28") (pin "2") (pinfunction "2_2") (pintype "passive"))
      (node (ref "U2") (pin "1") (pinfunction "PE2_1") (pintype "passive"))
    )
    (net (code "52") (name "/SPI2_MISO") (class "Default")
      (node (ref "R17") (pin "2") (pinfunction "2_2") (pintype "passive"))
    )
    (net (code "53") (name "/SPI2_MOSI") (class "Default")
      (node (ref "R16") (pin "2") (pinfunction "2_2") (pintype "passive"))
    )
    (net (code "54") (name "/SPI2_NSS") (class "Default")
      (node (ref "R19") (pin "2") (pinfunction "2_2") (pintype "passive"))
    )
    (net (code "55") (name "/SPI2_SCK") (class "Default")
      (node (ref "R18") (pin "2") (pinfunction "2_2") (pintype "passive"))
    )
    (net (code "56") (name "/TEMP_LED") (class "Default")
      (node (ref "R31") (pin "2") (pinfunction "2_2") (pintype "passive"))
      (node (ref "U2") (pin "4") (pinfunction "PE5_4") (pintype "passive"))
    )
    (net (code "57") (name "/VENV+") (class "Default")
      (node (ref "U2") (pin "36") (pinfunction "PB1/ADC_IN9/TIM3_CH4_36") (pintype "passive"))
    )
    (net (code "58") (name "/VENV-") (class "Default")
      (node (ref "U2") (pin "35") (pinfunction "PB0/ADC_IN8/TIM3_CH3_35") (pintype "passive"))
    )
    (net (code "59") (name "/VOLT_DEC") (class "Default")
      (node (ref "U2") (pin "18") (pinfunction "PC3/ADC_IN13_18") (pintype "passive"))
    )
    (net (code "60") (name "/VRMS+") (class "Default")
      (node (ref "U2") (pin "34") (pinfunction "PC5/ADC_IN15_34") (pintype "passive"))
    )
    (net (code "61") (name "/VRMS-") (class "Default")
      (node (ref "U2") (pin "33") (pinfunction "PC4/ADC_IN14_33") (pintype "passive"))
    )
    (net (code "62") (name "/VSWR_LED") (class "Default")
      (node (ref "R29") (pin "2") (pinfunction "2_2") (pintype "passive"))
      (node (ref "U2") (pin "2") (pinfunction "PE3_2") (pintype "passive"))
    )
    (net (code "63") (name "/W5500_INTn") (class "Default")
      (node (ref "U2") (pin "55") (pinfunction "PD8_55") (pintype "passive"))
    )
    (net (code "64") (name "/W5500_RSTn") (class "Default")
      (node (ref "U2") (pin "56") (pinfunction "PD9_56") (pintype "passive"))
    )
    (net (code "65") (name "3.3VCC") (class "Default")
      (node (ref "C1") (pin "2") (pinfunction "2_2") (pintype "passive"))
      (node (ref "C3") (pin "2") (pinfunction "2_2") (pintype "passive"))
      (node (ref "C4") (pin "2") (pinfunction "2_2") (pintype "passive"))
      (node (ref "C5") (pin "2") (pinfunction "2_2") (pintype "passive"))
      (node (ref "C6") (pin "2") (pinfunction "2_2") (pintype "passive"))
      (node (ref "C7") (pin "2") (pinfunction "2_2") (pintype "passive"))
      (node (ref "C8") (pin "2") (pinfunction "2_2") (pintype "passive"))
      (node (ref "C83") (pin "2") (pinfunction "2_2") (pintype "passive"))
      (node (ref "C9") (pin "2") (pinfunction "2_2") (pintype "passive"))
      (node (ref "J1") (pin "1") (pinfunction "1_1") (pintype "passive"))
      (node (ref "J3") (pin "1") (pinfunction "TX+_1") (pintype "passive"))
      (node (ref "R1") (pin "2") (pinfunction "2_2") (pintype "passive"))
      (node (ref "R2") (pin "2") (pinfunction "2_2") (pintype "passive"))
      (node (ref "R3") (pin "2") (pinfunction "2_2") (pintype "passive"))
      (node (ref "R4") (pin "2") (pinfunction "2_2") (pintype "passive"))
      (node (ref "R5") (pin "2") (pinfunction "2_2") (pintype "passive"))
      (node (ref "R6") (pin "2") (pinfunction "2_2") (pintype "passive"))
      (node (ref "R7") (pin "2") (pinfunction "2_2") (pintype "passive"))
      (node (ref "U1") (pin "8") (pinfunction "VCC_8") (pintype "passive"))
      (node (ref "U2") (pin "100") (pinfunction "VDD_3_100") (pintype "passive"))
      (node (ref "U2") (pin "11") (pinfunction "Vdd_5_11") (pintype "passive"))
      (node (ref "U2") (pin "22") (pinfunction "VDDA_22") (pintype "passive"))
      (node (ref "U2") (pin "28") (pinfunction "VDD_4_28") (pintype "passive"))
      (node (ref "U2") (pin "50") (pinfunction "VDD_1_50") (pintype "passive"))
      (node (ref "U2") (pin "6") (pinfunction "Vbat_6") (pintype "passive"))
      (node (ref "U2") (pin "75") (pinfunction "VDD_2_75") (pintype "passive"))
    )
    (net (code "66") (name "3.3VCC1") (class "Default")
      (node (ref "C102") (pin "1") (pinfunction "1_1") (pintype "passive"))
      (node (ref "C107") (pin "1") (pinfunction "1_1") (pintype "passive"))
      (node (ref "C108") (pin "1") (pinfunction "1_1") (pintype "passive"))
      (node (ref "C109") (pin "1") (pinfunction "1_1") (pintype "passive"))
      (node (ref "C110") (pin "1") (pinfunction "1_1") (pintype "passive"))
      (node (ref "C71") (pin "1") (pinfunction "1_1") (pintype "passive"))
      (node (ref "C90") (pin "1") (pinfunction "1_1") (pintype "passive"))
      (node (ref "C98") (pin "1") (pinfunction "1_1") (pintype "passive"))
      (node (ref "C99") (pin "1") (pinfunction "1_1") (pintype "passive"))
      (node (ref "FB10") (pin "1") (pinfunction "1_1") (pintype "passive"))
      (node (ref "FB11") (pin "1") (pinfunction "1_1") (pintype "passive"))
      (node (ref "FB12") (pin "1") (pinfunction "1_1") (pintype "passive"))
      (node (ref "FB2") (pin "1") (pinfunction "1_1") (pintype "passive"))
      (node (ref "FB3") (pin "1") (pinfunction "1_1") (pintype "passive"))
      (node (ref "FB4") (pin "1") (pinfunction "1_1") (pintype "passive"))
      (node (ref "FB5") (pin "1") (pinfunction "1_1") (pintype "passive"))
      (node (ref "FB6") (pin "1") (pinfunction "1_1") (pintype "passive"))
      (node (ref "FB9") (pin "1") (pinfunction "1_1") (pintype "passive"))
      (node (ref "L2") (pin "2") (pinfunction "2_2") (pintype "passive"))
      (node (ref "R119") (pin "1") (pinfunction "1_1") (pintype "passive"))
      (node (ref "R121") (pin "1") (pinfunction "1_1") (pintype "passive"))
      (node (ref "R13") (pin "1") (pinfunction "1_1") (pintype "passive"))
      (node (ref "R133") (pin "1") (pinfunction "1_1") (pintype "passive"))
      (node (ref "R175") (pin "1") (pinfunction "1_1") (pintype "passive"))
      (node (ref "R176") (pin "1") (pinfunction "1_1") (pintype "passive"))
      (node (ref "R20") (pin "1") (pinfunction "1_1") (pintype "passive"))
      (node (ref "R21") (pin "1") (pinfunction "1_1") (pintype "passive"))
      (node (ref "R22") (pin "1") (pinfunction "1_1") (pintype "passive"))
      (node (ref "R23") (pin "1") (pinfunction "1_1") (pintype "passive"))
      (node (ref "R24") (pin "1") (pinfunction "1_1") (pintype "passive"))
      (node (ref "R61") (pin "1") (pinfunction "1_1") (pintype "passive"))
      (node (ref "R62") (pin "1") (pinfunction "1_1") (pintype "passive"))
      (node (ref "R70") (pin "1") (pinfunction "1_1") (pintype "passive"))
      (node (ref "R79") (pin "1") (pinfunction "1_1") (pintype "passive"))
      (node (ref "R81") (pin "1") (pinfunction "1_1") (pintype "passive"))
      (node (ref "R91") (pin "1") (pinfunction "1_1") (pintype "passive"))
    )
    (net (code "67") (name "3.3VCC_REF") (class "Default")
      (node (ref "U2") (pin "21") (pinfunction "Vref+_21") (pintype "passive"))
    )
    (net (code "68") (name "GND") (class "Default")
      (node (ref "C1") (pin "1") (pinfunction "1_1") (pintype "passive"))
      (node (ref "C10") (pin "2") (pinfunction "2_2") (pintype "passive"))
      (node (ref "C102") (pin "2") (pinfunction "2_2") (pintype "passive"))
      (node (ref "C107") (pin "2") (pinfunction "2_2") (pintype "passive"))
      (node (ref "C108") (pin "2") (pinfunction "2_2") (pintype "passive"))
      (node (ref "C109") (pin "2") (pinfunction "2_2") (pintype "passive"))
      (node (ref "C11") (pin "2") (pinfunction "2_2") (pintype "passive"))
      (node (ref "C110") (pin "2") (pinfunction "2_2") (pintype "passive"))
      (node (ref "C2") (pin "1") (pinfunction "1_1") (pintype "passive"))
      (node (ref "C3") (pin "1") (pinfunction "1_1") (pintype "passive"))
      (node (ref "C4") (pin "1") (pinfunction "1_1") (pintype "passive"))
      (node (ref "C5") (pin "1") (pinfunction "1_1") (pintype "passive"))
      (node (ref "C6") (pin "1") (pinfunction "1_1") (pintype "passive"))
      (node (ref "C7") (pin "1") (pinfunction "1_1") (pintype "passive"))
      (node (ref "C71") (pin "2") (pinfunction "2_2") (pintype "passive"))
      (node (ref "C8") (pin "1") (pinfunction "1_1") (pintype "passive"))
      (node (ref "C83") (pin "1") (pinfunction "1_1") (pintype "passive"))
      (node (ref "C9") (pin "1") (pinfunction "1_1") (pintype "passive"))
      (node (ref "C90") (pin "2") (pinfunction "2_2") (pintype "passive"))
      (node (ref "C98") (pin "2") (pinfunction "2_2") (pintype "passive"))
      (node (ref "C99") (pin "2") (pinfunction "2_2") (pintype "passive"))
      (node (ref "D2") (pin "2") (pinfunction "2_2") (pintype "passive"))
      (node (ref "D3") (pin "2") (pinfunction "2_2") (pintype "passive"))
      (node (ref "D4") (pin "2") (pinfunction "2_2") (pintype "passive"))
      (node (ref "D5") (pin "2") (pinfunction "2_2") (pintype "passive"))
      (node (ref "D6") (pin "2") (pinfunction "2_2") (pintype "passive"))
      (node (ref "D7") (pin "2") (pinfunction "2_2") (pintype "passive"))
      (node (ref "D8") (pin "2") (pinfunction "2_2") (pintype "passive"))
      (node (ref "D9") (pin "2") (pinfunction "2_2") (pintype "passive"))
      (node (ref "J1") (pin "6") (pinfunction "6_6") (pintype "passive"))
      (node (ref "J10") (pin "3") (pinfunction "3_3") (pintype "passive"))
      (node (ref "J11") (pin "3") (pinfunction "3_3") (pintype "passive"))
      (node (ref "J12") (pin "3") (pinfunction "3_3") (pintype "passive"))
      (node (ref "J13") (pin "3") (pinfunction "3_3") (pintype "passive"))
      (node (ref "J14") (pin "3") (pinfunction "3_3") (pintype "passive"))
      (node (ref "J2") (pin "8") (pinfunction "8_8") (pintype "passive"))
      (node (ref "J3") (pin "13") (pinfunction "13_13") (pintype "passive"))
      (node (ref "J3") (pin "14") (pinfunction "14_14") (pintype "passive"))
      (node (ref "J3") (pin "6") (pinfunction "RX-_6") (pintype "passive"))
      (node (ref "J5") (pin "3") (pinfunction "3_3") (pintype "passive"))
      (node (ref "J6") (pin "3") (pinfunction "3_3") (pintype "passive"))
      (node (ref "J8") (pin "3") (pinfunction "3_3") (pintype "passive"))
      (node (ref "J9") (pin "3") (pinfunction "3_3") (pintype "passive"))
      (node (ref "R10") (pin "1") (pinfunction "1_1") (pintype "passive"))
      (node (ref "R15") (pin "1") (pinfunction "1_1") (pintype "passive"))
      (node (ref "R8") (pin "1") (pinfunction "1_1") (pintype "passive"))
      (node (ref "S1") (pin "1") (pinfunction "1_1") (pintype "passive"))
      (node (ref "S1") (pin "2") (pinfunction "2_2") (pintype "passive"))
      (node (ref "S1") (pin "3") (pinfunction "3_3") (pintype "passive"))
      (node (ref "S1") (pin "4") (pinfunction "4_4") (pintype "passive"))
      (node (ref "S1") (pin "5") (pinfunction "5_5") (pintype "passive"))
      (node (ref "S1") (pin "6") (pinfunction "6_6") (pintype "passive"))
      (node (ref "S1") (pin "7") (pinfunction "7_7") (pintype "passive"))
      (node (ref "S1") (pin "8") (pinfunction "8_8") (pintype "passive"))
      (node (ref "U1") (pin "1") (pinfunction "A0_1") (pintype "passive"))
      (node (ref "U1") (pin "2") (pinfunction "A1_2") (pintype "passive"))
      (node (ref "U1") (pin "3") (pinfunction "A2_3") (pintype "passive"))
      (node (ref "U1") (pin "4") (pinfunction "GND_4") (pintype "passive"))
      (node (ref "U1") (pin "7") (pinfunction "WP_7") (pintype "passive"))
      (node (ref "U2") (pin "10") (pinfunction "Vss_5_10") (pintype "passive"))
      (node (ref "U2") (pin "19") (pinfunction "VssA_19") (pintype "passive"))
      (node (ref "U2") (pin "20") (pinfunction "Vref-_20") (pintype "passive"))
      (node (ref "U2") (pin "27") (pinfunction "VSS_4_27") (pintype "passive"))
      (node (ref "U2") (pin "49") (pinfunction "VSS_1_49") (pintype "passive"))
      (node (ref "U2") (pin "74") (pinfunction "VSS-2_74") (pintype "passive"))
      (node (ref "U2") (pin "99") (pinfunction "VSS_3_99") (pintype "passive"))
    )
    (net (code "69") (name "Net-(FB2-Pad2)") (class "Default")
      (node (ref "FB2") (pin "2") (pinfunction "2_2") (pintype "passive"))
      (node (ref "J5") (pin "1") (pinfunction "1_1") (pintype "passive"))
    )
    (net (code "70") (name "Net-(FB3-Pad2)") (class "Default")
      (node (ref "FB3") (pin "2") (pinfunction "2_2") (pintype "passive"))
      (node (ref "J11") (pin "1") (pinfunction "1_1") (pintype "passive"))
    )
    (net (code "71") (name "Net-(FB4-Pad2)") (class "Default")
      (node (ref "FB4") (pin "2") (pinfunction "2_2") (pintype "passive"))
      (node (ref "J6") (pin "1") (pinfunction "1_1") (pintype "passive"))
    )
    (net (code "72") (name "Net-(FB5-Pad2)") (class "Default")
      (node (ref "FB5") (pin "2") (pinfunction "2_2") (pintype "passive"))
      (node (ref "J12") (pin "1") (pinfunction "1_1") (pintype "passive"))
    )
    (net (code "73") (name "Net-(FB6-Pad2)") (class "Default")
      (node (ref "FB6") (pin "2") (pinfunction "2_2") (pintype "passive"))
      (node (ref "J8") (pin "1") (pinfunction "1_1") (pintype "passive"))
    )
    (net (code "74") (name "Net-(FB9-Pad2)") (class "Default")
      (node (ref "FB9") (pin "2") (pinfunction "2_2") (pintype "passive"))
      (node (ref "J13") (pin "1") (pinfunction "1_1") (pintype "passive"))
    )
    (net (code "75") (name "Net-(FB10-Pad2)") (class "Default")
      (node (ref "FB10") (pin "2") (pinfunction "2_2") (pintype "passive"))
      (node (ref "J9") (pin "1") (pinfunction "1_1") (pintype "passive"))
    )
    (net (code "76") (name "Net-(FB11-Pad2)") (class "Default")
      (node (ref "FB11") (pin "2") (pinfunction "2_2") (pintype "passive"))
      (node (ref "J14") (pin "1") (pinfunction "1_1") (pintype "passive"))
    )
    (net (code "77") (name "Net-(FB12-Pad2)") (class "Default")
      (node (ref "FB12") (pin "2") (pinfunction "2_2") (pintype "passive"))
      (node (ref "J10") (pin "1") (pinfunction "1_1") (pintype "passive"))
    )
    (net (code "78") (name "Net-(J2-Pad1)") (class "Default")
      (node (ref "J2") (pin "1") (pinfunction "1_1") (pintype "passive"))
      (node (ref "R26") (pin "1") (pinfunction "1_1") (pintype "passive"))
    )
    (net (code "79") (name "Net-(J2-Pad2)") (class "Default")
      (node (ref "J2") (pin "2") (pinfunction "2_2") (pintype "passive"))
      (node (ref "R28") (pin "1") (pinfunction "1_1") (pintype "passive"))
    )
    (net (code "80") (name "Net-(J2-Pad3)") (class "Default")
      (node (ref "J2") (pin "3") (pinfunction "3_3") (pintype "passive"))
      (node (ref "R29") (pin "1") (pinfunction "1_1") (pintype "passive"))
    )
    (net (code "81") (name "Net-(J2-Pad4)") (class "Default")
      (node (ref "J2") (pin "4") (pinfunction "4_4") (pintype "passive"))
      (node (ref "R30") (pin "1") (pinfunction "1_1") (pintype "passive"))
    )
    (net (code "82") (name "Net-(J2-Pad5)") (class "Default")
      (node (ref "J2") (pin "5") (pinfunction "5_5") (pintype "passive"))
      (node (ref "R31") (pin "1") (pinfunction "1_1") (pintype "passive"))
    )
    (net (code "83") (name "Net-(J2-Pad6)") (class "Default")
      (node (ref "J2") (pin "6") (pinfunction "6_6") (pintype "passive"))
      (node (ref "R32") (pin "1") (pinfunction "1_1") (pintype "passive"))
    )
    (net (code "84") (name "Net-(J2-Pad7)") (class "Default")
      (node (ref "J2") (pin "7") (pinfunction "7_7") (pintype "passive"))
      (node (ref "L2") (pin "1") (pinfunction "1_1") (pintype "passive"))
    )
    (net (code "85") (name "Net-(TP9-TP)") (class "Default")
      (node (ref "TP9") (pin "1") (pinfunction "TP_1") (pintype "passive"))
      (node (ref "U2") (pin "63") (pinfunction "PC6_63") (pintype "passive"))
    )
    (net (code "86") (name "Net-(TP10-TP)") (class "Default")
      (node (ref "TP10") (pin "1") (pinfunction "TP_1") (pintype "passive"))
      (node (ref "U2") (pin "61") (pinfunction "PD14_61") (pintype "passive"))
    )
    (net (code "87") (name "Net-(TP11-TP)") (class "Default")
      (node (ref "TP11") (pin "1") (pinfunction "TP_1") (pintype "passive"))
      (node (ref "U2") (pin "62") (pinfunction "PD15_62") (pintype "passive"))
    )
    (net (code "88") (name "Net-(TP12-TP)") (class "Default")
      (node (ref "TP12") (pin "1") (pinfunction "TP_1") (pintype "passive"))
      (node (ref "U2") (pin "30") (pinfunction "PA5/SPI1_SCK/ADC_IN5_30") (pintype "passive"))
    )
    (net (code "89") (name "Net-(TP13-TP)") (class "Default")
      (node (ref "TP13") (pin "1") (pinfunction "TP_1") (pintype "passive"))
      (node (ref "U2") (pin "15") (pinfunction "PC0/ADC_IN10_15") (pintype "passive"))
    )
    (net (code "90") (name "Net-(TP14-TP)") (class "Default")
      (node (ref "TP14") (pin "1") (pinfunction "TP_1") (pintype "passive"))
      (node (ref "U2") (pin "16") (pinfunction "PC1/ADC_IN11_16") (pintype "passive"))
    )
    (net (code "91") (name "Net-(TP21-TP)") (class "Default")
      (node (ref "TP21") (pin "1") (pinfunction "TP_1") (pintype "passive"))
      (node (ref "U2") (pin "29") (pinfunction "PA4/SPI1_NSS/USART2_CK/ADC_IN4_29") (pintype "passive"))
    )
    (net (code "92") (name "Net-(U2-OSC_IN)") (class "Default")
      (node (ref "C10") (pin "1") (pinfunction "1_1") (pintype "passive"))
      (node (ref "U2") (pin "12") (pinfunction "OSC_IN_12") (pintype "passive"))
      (node (ref "X1") (pin "2") (pinfunction "OSC2_2") (pintype "passive"))
    )
    (net (code "93") (name "Net-(U2-OSC_OUT)") (class "Default")
      (node (ref "C11") (pin "1") (pinfunction "1_1") (pintype "passive"))
      (node (ref "U2") (pin "13") (pinfunction "OSC_OUT_13") (pintype "passive"))
      (node (ref "X1") (pin "1") (pinfunction "OSC1_1") (pintype "passive"))
    )
    (net (code "94") (name "Net-(U2-PB2{slash}BOOT1)") (class "Default")
      (node (ref "R15") (pin "2") (pinfunction "2_2") (pintype "passive"))
      (node (ref "U2") (pin "37") (pinfunction "PB2/BOOT1_37") (pintype "passive"))
    )
    (net (code "95") (name "Net-(U2-PB6{slash}I2C1_SCL{slash}TIM4_CH1)") (class "Default")
      (node (ref "R12") (pin "1") (pinfunction "1_1") (pintype "passive"))
      (node (ref "U2") (pin "92") (pinfunction "PB6/I2C1_SCL/TIM4_CH1_92") (pintype "passive"))
    )
    (net (code "96") (name "Net-(U2-PB7{slash}IC21_SDA{slash}TIM4_CH2)") (class "Default")
      (node (ref "R11") (pin "1") (pinfunction "1_1") (pintype "passive"))
      (node (ref "U2") (pin "93") (pinfunction "PB7/IC21_SDA/TIM4_CH2_93") (pintype "passive"))
    )
    (net (code "97") (name "Net-(U2-PB12{slash}SPI2_NSS{slash}I2C2_SMBAI{slash}USART3_CK{slash}TIM1_BKIN{slash}CAN2_RX)") (class "Default")
      (node (ref "R19") (pin "1") (pinfunction "1_1") (pintype "passive"))
      (node (ref "U2") (pin "51") (pinfunction "PB12/SPI2_NSS/I2C2_SMBAI/USART3_CK/TIM1_BKIN/CAN2_RX_51") (pintype "passive"))
    )
    (net (code "98") (name "Net-(U2-PB13{slash}SPI2_SCK{slash}USART3_CTS{slash}TIM1_CH1N{slash}CAN2_TX)") (class "Default")
      (node (ref "R18") (pin "1") (pinfunction "1_1") (pintype "passive"))
      (node (ref "U2") (pin "52") (pinfunction "PB13/SPI2_SCK/USART3_CTS/TIM1_CH1N/CAN2_TX_52") (pintype "passive"))
    )
    (net (code "99") (name "Net-(U2-PB14{slash}SPI2_MISO{slash}USART3_RTS{slash}TIM1_CH2N)") (class "Default")
      (node (ref "R17") (pin "1") (pinfunction "1_1") (pintype "passive"))
      (node (ref "U2") (pin "53") (pinfunction "PB14/SPI2_MISO/USART3_RTS/TIM1_CH2N_53") (pintype "passive"))
    )
    (net (code "100") (name "Net-(U2-PB15{slash}SPI2_MOSI{slash}TIM1_CH3N)") (class "Default")
      (node (ref "R16") (pin "1") (pinfunction "1_1") (pintype "passive"))
      (node (ref "U2") (pin "54") (pinfunction "PB15/SPI2_MOSI/TIM1_CH3N_54") (pintype "passive"))
    )
    (net (code "101") (name "Net-(U2-PC7)") (class "Default")
      (node (ref "R77") (pin "1") (pinfunction "1_1") (pintype "passive"))
      (node (ref "U2") (pin "64") (pinfunction "PC7_64") (pintype "passive"))
    )
    (net (code "102") (name "Net-(U2-PC12)") (class "Default")
      (node (ref "R117") (pin "1") (pinfunction "1_1") (pintype "passive"))
      (node (ref "U2") (pin "80") (pinfunction "PC12_80") (pintype "passive"))
    )
    (net (code "103") (name "Net-(U2-PD0)") (class "Default")
      (node (ref "R116") (pin "1") (pinfunction "1_1") (pintype "passive"))
      (node (ref "U2") (pin "81") (pinfunction "PD0_81") (pintype "passive"))
    )
    (net (code "104") (name "Net-(U2-PD1)") (class "Default")
      (node (ref "R115") (pin "1") (pinfunction "1_1") (pintype "passive"))
      (node (ref "U2") (pin "82") (pinfunction "PD1_82") (pintype "passive"))
    )
    (net (code "105") (name "Net-(U2-PD2{slash}TIM3_ETR)") (class "Default")
      (node (ref "R114") (pin "1") (pinfunction "1_1") (pintype "passive"))
      (node (ref "U2") (pin "83") (pinfunction "PD2/TIM3_ETR_83") (pintype "passive"))
    )
    (net (code "106") (name "Net-(U2-PD3)") (class "Default")
      (node (ref "R113") (pin "1") (pinfunction "1_1") (pintype "passive"))
      (node (ref "U2") (pin "84") (pinfunction "PD3_84") (pintype "passive"))
    )
    (net (code "107") (name "Net-(U2-PD4)") (class "Default")
      (node (ref "R112") (pin "1") (pinfunction "1_1") (pintype "passive"))
      (node (ref "U2") (pin "85") (pinfunction "PD4_85") (pintype "passive"))
    )
    (net (code "108") (name "Net-(U2-PD5)") (class "Default")
      (node (ref "R111") (pin "1") (pinfunction "1_1") (pintype "passive"))
      (node (ref "U2") (pin "86") (pinfunction "PD5_86") (pintype "passive"))
    )
    (net (code "109") (name "Net-(U2-PD6)") (class "Default")
      (node (ref "R110") (pin "1") (pinfunction "1_1") (pintype "passive"))
      (node (ref "U2") (pin "87") (pinfunction "PD6_87") (pintype "passive"))
    )
    (net (code "110") (name "Net-(U2-PD7)") (class "Default")
      (node (ref "R109") (pin "1") (pinfunction "1_1") (pintype "passive"))
      (node (ref "U2") (pin "88") (pinfunction "PD7_88") (pintype "passive"))
    )
    (net (code "111") (name "unconnected-(J3-A1-Pad10)") (class "Default")
      (node (ref "J3") (pin "10") (pinfunction "A1_10") (pintype "passive"))
    )
    (net (code "112") (name "unconnected-(J3-A2-Pad12)") (class "Default")
      (node (ref "J3") (pin "12") (pinfunction "A2_12") (pintype "passive"))
    )
    (net (code "113") (name "unconnected-(J3-K1-Pad9)") (class "Default")
      (node (ref "J3") (pin "9") (pinfunction "K1_9") (pintype "passive"))
    )
    (net (code "114") (name "unconnected-(J3-K2-Pad11)") (class "Default")
      (node (ref "J3") (pin "11") (pinfunction "K2_11") (pintype "passive"))
    )
    (net (code "115") (name "unconnected-(J3-Pad15)") (class "Default")
      (node (ref "J3") (pin "15") (pinfunction "15_15") (pintype "passive+no_connect"))
    )
    (net (code "116") (name "unconnected-(J3-Pad16)") (class "Default")
      (node (ref "J3") (pin "16") (pinfunction "16_16") (pintype "passive+no_connect"))
    )
    (net (code "117") (name "unconnected-(U2-NC-Pad73)") (class "Default")
      (node (ref "U2") (pin "73") (pinfunction "NC_73") (pintype "passive"))
    )
    (net (code "118") (name "unconnected-(U2-PA6{slash}SPI1_MISO{slash}ADC_IN6{slash}TIM3_CH1-Pad31)") (class "Default")
      (node (ref "U2") (pin "31") (pinfunction "PA6/SPI1_MISO/ADC_IN6/TIM3_CH1_31") (pintype "passive"))
    )
    (net (code "119") (name "unconnected-(U2-PA7{slash}SPI1_MOSI{slash}ADC_IN7{slash}TIM3_CH2-Pad32)") (class "Default")
      (node (ref "U2") (pin "32") (pinfunction "PA7/SPI1_MOSI/ADC_IN7/TIM3_CH2_32") (pintype "passive"))
    )
    (net (code "120") (name "unconnected-(U2-PA8{slash}USART1_CK{slash}TIM1_CH1{slash}MCO-Pad67)") (class "Default")
      (node (ref "U2") (pin "67") (pinfunction "PA8/USART1_CK/TIM1_CH1/MCO_67") (pintype "passive"))
    )
    (net (code "121") (name "unconnected-(U2-PB5{slash}I2C1_SMBAI-Pad91)") (class "Default")
      (node (ref "U2") (pin "91") (pinfunction "PB5/I2C1_SMBAI_91") (pintype "passive"))
    )
    (net (code "122") (name "unconnected-(U2-PB8{slash}TIM4_CH3-Pad95)") (class "Default")
      (node (ref "U2") (pin "95") (pinfunction "PB8/TIM4_CH3_95") (pintype "passive"))
    )
    (net (code "123") (name "unconnected-(U2-PB9{slash}TIM4_CH4-Pad96)") (class "Default")
      (node (ref "U2") (pin "96") (pinfunction "PB9/TIM4_CH4_96") (pintype "passive"))
    )
    (net (code "124") (name "unconnected-(U2-PB10{slash}I2C2_SCL{slash}USART3_TX-Pad47)") (class "Default")
      (node (ref "U2") (pin "47") (pinfunction "PB10/I2C2_SCL/USART3_TX_47") (pintype "passive"))
    )
    (net (code "125") (name "unconnected-(U2-PB11{slash}I2C2_SDA{slash}USART3_RX-Pad48)") (class "Default")
      (node (ref "U2") (pin "48") (pinfunction "PB11/I2C2_SDA/USART3_RX_48") (pintype "passive"))
    )
    (net (code "126") (name "unconnected-(U2-PC2{slash}ADC_IN12-Pad17)") (class "Default")
      (node (ref "U2") (pin "17") (pinfunction "PC2/ADC_IN12_17") (pintype "passive"))
    )
    (net (code "127") (name "unconnected-(U2-PC8-Pad65)") (class "Default")
      (node (ref "U2") (pin "65") (pinfunction "PC8_65") (pintype "passive"))
    )
    (net (code "128") (name "unconnected-(U2-PC9-Pad66)") (class "Default")
      (node (ref "U2") (pin "66") (pinfunction "PC9_66") (pintype "passive"))
    )
    (net (code "129") (name "unconnected-(U2-PC10-Pad78)") (class "Default")
      (node (ref "U2") (pin "78") (pinfunction "PC10_78") (pintype "passive"))
    )
    (net (code "130") (name "unconnected-(U2-PC11-Pad79)") (class "Default")
      (node (ref "U2") (pin "79") (pinfunction "PC11_79") (pintype "passive"))
    )
    (net (code "131") (name "unconnected-(U2-PC13{slash}ANTI_TAMP-Pad7)") (class "Default")
      (node (ref "U2") (pin "7") (pinfunction "PC13/ANTI_TAMP_7") (pintype "passive"))
    )
    (net (code "132") (name "unconnected-(U2-PC14{slash}OSC32_IN-Pad8)") (class "Default")
      (node (ref "U2") (pin "8") (pinfunction "PC14/OSC32_IN_8") (pintype "passive"))
    )
    (net (code "133") (name "unconnected-(U2-PC15{slash}OSC32_OUT-Pad9)") (class "Default")
      (node (ref "U2") (pin "9") (pinfunction "PC15/OSC32_OUT_9") (pintype "passive"))
    )
    (net (code "134") (name "unconnected-(U2-PD10-Pad57)") (class "Default")
      (node (ref "U2") (pin "57") (pinfunction "PD10_57") (pintype "passive"))
    )
    (net (code "135") (name "unconnected-(U2-PD11-Pad58)") (class "Default")
      (node (ref "U2") (pin "58") (pinfunction "PD11_58") (pintype "passive"))
    )
    (net (code "136") (name "unconnected-(U2-PD12-Pad59)") (class "Default")
      (node (ref "U2") (pin "59") (pinfunction "PD12_59") (pintype "passive"))
    )
    (net (code "137") (name "unconnected-(U2-PD13-Pad60)") (class "Default")
      (node (ref "U2") (pin "60") (pinfunction "PD13_60") (pintype "passive"))
    )
    (net (code "138") (name "unconnected-(U2-PE0{slash}TIM4_ETR-Pad97)") (class "Default")
      (node (ref "U2") (pin "97") (pinfunction "PE0/TIM4_ETR_97") (pintype "passive"))
    )
    (net (code "139") (name "unconnected-(U2-PE7-Pad38)") (class "Default")
      (node (ref "U2") (pin "38") (pinfunction "PE7_38") (pintype "passive"))
    )
  )
)
